# AD9833_Diff_Output_Current_Source.net
KiCad netlist of a schematic drawn in Altium Designer
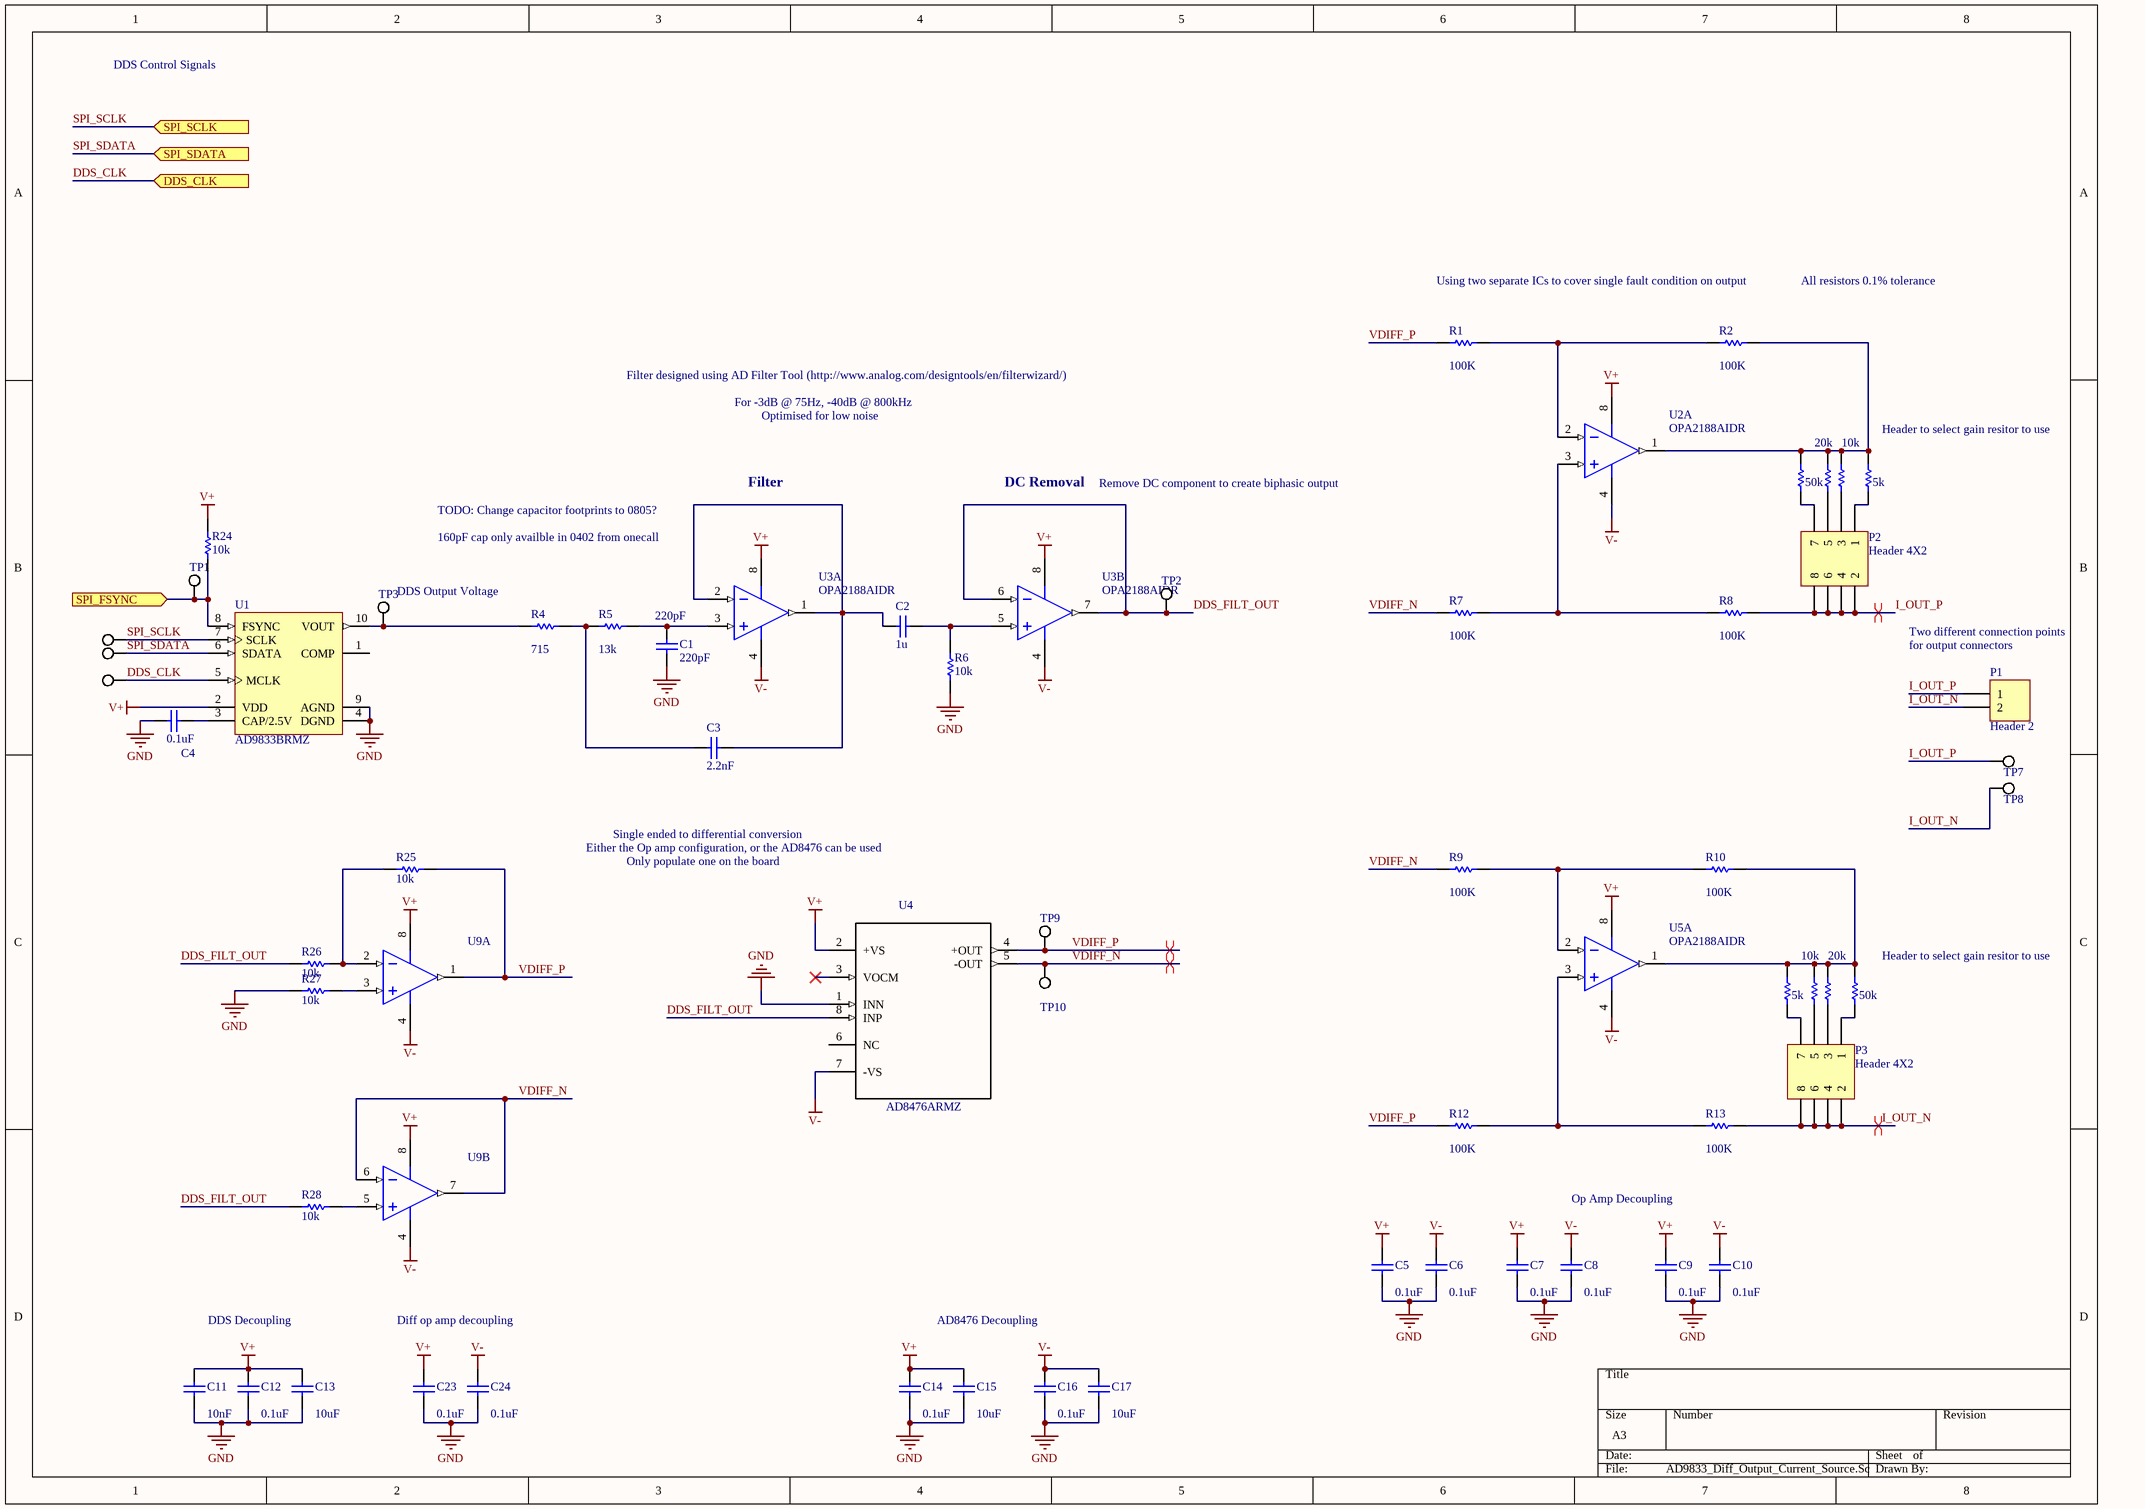
[diagram p0: AD9833_Diff_Output_Current_Source.SchDoc]

(export (version "E")
  (design (tool "Eeschema 10.0.6"))
  (components
    (comp (ref "C1")
      (value "220pF")
      (footprint "1608[0603]")
      (description "Capacitor (Semiconductor SIM Model)")
      (fields (field (name "ALTIUM_VALUE") "220pF") (field (name "PUBLISHER") "Altium Limited"))
      (libsource (lib "Miscellaneous Devices") (part "Cap Semi"))
    )
    (comp (ref "C2")
      (value "1u")
      (footprint "1608[0603]")
      (description "Capacitor (Semiconductor SIM Model)")
      (fields (field (name "PUBLISHER") "Altium Limited"))
      (libsource (lib "Miscellaneous Devices") (part "Cap Semi"))
    )
    (comp (ref "C3")
      (value "2.2nF")
      (footprint "1608[0603]")
      (description "Capacitor (Semiconductor SIM Model)")
      (fields (field (name "PUBLISHER") "Altium Limited"))
      (libsource (lib "Miscellaneous Devices") (part "Cap Semi"))
    )
    (comp (ref "C4")
      (value "0.1uF")
      (footprint "1608[0603]")
      (description "Capacitor (Semiconductor SIM Model)")
      (fields (field (name "PUBLISHER") "Altium Limited"))
      (libsource (lib "Miscellaneous Devices") (part "Cap Semi"))
    )
    (comp (ref "C5")
      (value "0.1uF")
      (footprint "1608[0603]")
      (description "Capacitor (Semiconductor SIM Model)")
      (fields (field (name "PUBLISHER") "Altium Limited"))
      (libsource (lib "Miscellaneous Devices") (part "Cap Semi"))
    )
    (comp (ref "C6")
      (value "0.1uF")
      (footprint "1608[0603]")
      (description "Capacitor (Semiconductor SIM Model)")
      (fields (field (name "PUBLISHER") "Altium Limited"))
      (libsource (lib "Miscellaneous Devices") (part "Cap Semi"))
    )
    (comp (ref "C7")
      (value "0.1uF")
      (footprint "1608[0603]")
      (description "Capacitor (Semiconductor SIM Model)")
      (fields (field (name "PUBLISHER") "Altium Limited"))
      (libsource (lib "Miscellaneous Devices") (part "Cap Semi"))
    )
    (comp (ref "C8")
      (value "0.1uF")
      (footprint "1608[0603]")
      (description "Capacitor (Semiconductor SIM Model)")
      (fields (field (name "PUBLISHER") "Altium Limited"))
      (libsource (lib "Miscellaneous Devices") (part "Cap Semi"))
    )
    (comp (ref "C9")
      (value "0.1uF")
      (footprint "1608[0603]")
      (description "Capacitor (Semiconductor SIM Model)")
      (fields (field (name "PUBLISHER") "Altium Limited"))
      (libsource (lib "Miscellaneous Devices") (part "Cap Semi"))
    )
    (comp (ref "C10")
      (value "0.1uF")
      (footprint "1608[0603]")
      (description "Capacitor (Semiconductor SIM Model)")
      (fields (field (name "PUBLISHER") "Altium Limited"))
      (libsource (lib "Miscellaneous Devices") (part "Cap Semi"))
    )
    (comp (ref "C11")
      (value "10nF")
      (footprint "1608[0603]")
      (description "Capacitor (Semiconductor SIM Model)")
      (fields (field (name "PUBLISHER") "Altium Limited"))
      (libsource (lib "Miscellaneous Devices") (part "Cap Semi"))
    )
    (comp (ref "C12")
      (value "0.1uF")
      (footprint "1608[0603]")
      (description "Capacitor (Semiconductor SIM Model)")
      (fields (field (name "PUBLISHER") "Altium Limited"))
      (libsource (lib "Miscellaneous Devices") (part "Cap Semi"))
    )
    (comp (ref "C13")
      (value "10uF")
      (footprint "1608[0603]")
      (description "Capacitor (Semiconductor SIM Model)")
      (fields (field (name "PUBLISHER") "Altium Limited"))
      (libsource (lib "Miscellaneous Devices") (part "Cap Semi"))
    )
    (comp (ref "C14")
      (value "0.1uF")
      (footprint "1608[0603]")
      (description "Capacitor (Semiconductor SIM Model)")
      (fields (field (name "PUBLISHER") "Altium Limited"))
      (libsource (lib "Miscellaneous Devices") (part "Cap Semi"))
    )
    (comp (ref "C15")
      (value "10uF")
      (footprint "1608[0603]")
      (description "Capacitor (Semiconductor SIM Model)")
      (fields (field (name "PUBLISHER") "Altium Limited"))
      (libsource (lib "Miscellaneous Devices") (part "Cap Semi"))
    )
    (comp (ref "C16")
      (value "0.1uF")
      (footprint "1608[0603]")
      (description "Capacitor (Semiconductor SIM Model)")
      (fields (field (name "PUBLISHER") "Altium Limited"))
      (libsource (lib "Miscellaneous Devices") (part "Cap Semi"))
    )
    (comp (ref "C17")
      (value "10uF")
      (footprint "1608[0603]")
      (description "Capacitor (Semiconductor SIM Model)")
      (fields (field (name "PUBLISHER") "Altium Limited"))
      (libsource (lib "Miscellaneous Devices") (part "Cap Semi"))
    )
    (comp (ref "C23")
      (value "0.1uF")
      (footprint "1608[0603]")
      (description "Capacitor (Semiconductor SIM Model)")
      (fields (field (name "PUBLISHER") "Altium Limited"))
      (libsource (lib "Miscellaneous Devices") (part "Cap Semi"))
    )
    (comp (ref "C24")
      (value "0.1uF")
      (footprint "1608[0603]")
      (description "Capacitor (Semiconductor SIM Model)")
      (fields (field (name "PUBLISHER") "Altium Limited"))
      (libsource (lib "Miscellaneous Devices") (part "Cap Semi"))
    )
    (comp (ref "P1")
      (value "Header 2")
      (footprint "HDR1X2")
      (description "Header, 2-Pin")
      (fields (field (name "PUBLISHER") "Altium Limited"))
      (libsource (lib "Miscellaneous Connectors") (part "Header 2"))
    )
    (comp (ref "P2")
      (value "Header 4X2")
      (footprint "HDR2X4")
      (description "Header, 4-Pin, Dual row")
      (fields (field (name "PUBLISHER") "Altium Limited"))
      (libsource (lib "Miscellaneous Connectors") (part "Header 4X2"))
    )
    (comp (ref "P3")
      (value "Header 4X2")
      (footprint "HDR2X4")
      (description "Header, 4-Pin, Dual row")
      (fields (field (name "PUBLISHER") "Altium Limited"))
      (libsource (lib "Miscellaneous Connectors") (part "Header 4X2"))
    )
    (comp (ref "R1")
      (value "100K")
      (footprint "6-0805_M")
      (description "Resistor")
      (fields (field (name "PUBLISHER") "Altium Limited"))
      (libsource (lib "Miscellaneous Devices") (part "Res1"))
    )
    (comp (ref "R2")
      (value "100K")
      (footprint "6-0805_M")
      (description "Resistor")
      (fields (field (name "PUBLISHER") "Altium Limited"))
      (libsource (lib "Miscellaneous Devices") (part "Res1"))
    )
    (comp (ref "R3")
      (value "50k")
      (footprint "6-0805_M")
      (description "Resistor")
      (fields (field (name "PUBLISHER") "Altium Limited"))
      (libsource (lib "Miscellaneous Devices") (part "Res1"))
    )
    (comp (ref "R4")
      (value "715")
      (footprint "6-0805_M")
      (description "Resistor")
      (fields (field (name "PUBLISHER") "Altium Limited"))
      (libsource (lib "Miscellaneous Devices") (part "Res1"))
    )
    (comp (ref "R5")
      (value "13k")
      (footprint "6-0805_M")
      (description "Resistor")
      (fields (field (name "PUBLISHER") "Altium Limited"))
      (libsource (lib "Miscellaneous Devices") (part "Res1"))
    )
    (comp (ref "R6")
      (value "10k")
      (footprint "6-0805_M")
      (description "Resistor")
      (fields (field (name "PUBLISHER") "Altium Limited"))
      (libsource (lib "Miscellaneous Devices") (part "Res1"))
    )
    (comp (ref "R7")
      (value "100K")
      (footprint "6-0805_M")
      (description "Resistor")
      (fields (field (name "PUBLISHER") "Altium Limited"))
      (libsource (lib "Miscellaneous Devices") (part "Res1"))
    )
    (comp (ref "R8")
      (value "100K")
      (footprint "6-0805_M")
      (description "Resistor")
      (fields (field (name "PUBLISHER") "Altium Limited"))
      (libsource (lib "Miscellaneous Devices") (part "Res1"))
    )
    (comp (ref "R9")
      (value "100K")
      (footprint "6-0805_M")
      (description "Resistor")
      (fields (field (name "PUBLISHER") "Altium Limited"))
      (libsource (lib "Miscellaneous Devices") (part "Res1"))
    )
    (comp (ref "R10")
      (value "100K")
      (footprint "6-0805_M")
      (description "Resistor")
      (fields (field (name "PUBLISHER") "Altium Limited"))
      (libsource (lib "Miscellaneous Devices") (part "Res1"))
    )
    (comp (ref "R11")
      (value "20k")
      (footprint "6-0805_M")
      (description "Resistor")
      (fields (field (name "PUBLISHER") "Altium Limited"))
      (libsource (lib "Miscellaneous Devices") (part "Res1"))
    )
    (comp (ref "R12")
      (value "100K")
      (footprint "6-0805_M")
      (description "Resistor")
      (fields (field (name "PUBLISHER") "Altium Limited"))
      (libsource (lib "Miscellaneous Devices") (part "Res1"))
    )
    (comp (ref "R13")
      (value "100K")
      (footprint "6-0805_M")
      (description "Resistor")
      (fields (field (name "PUBLISHER") "Altium Limited"))
      (libsource (lib "Miscellaneous Devices") (part "Res1"))
    )
    (comp (ref "R18")
      (value "10k")
      (footprint "6-0805_M")
      (description "Resistor")
      (fields (field (name "PUBLISHER") "Altium Limited"))
      (libsource (lib "Miscellaneous Devices") (part "Res1"))
    )
    (comp (ref "R19")
      (value "5k")
      (footprint "6-0805_M")
      (description "Resistor")
      (fields (field (name "PUBLISHER") "Altium Limited"))
      (libsource (lib "Miscellaneous Devices") (part "Res1"))
    )
    (comp (ref "R20")
      (value "5k")
      (footprint "6-0805_M")
      (description "Resistor")
      (fields (field (name "PUBLISHER") "Altium Limited"))
      (libsource (lib "Miscellaneous Devices") (part "Res1"))
    )
    (comp (ref "R21")
      (value "10k")
      (footprint "6-0805_M")
      (description "Resistor")
      (fields (field (name "PUBLISHER") "Altium Limited"))
      (libsource (lib "Miscellaneous Devices") (part "Res1"))
    )
    (comp (ref "R22")
      (value "20k")
      (footprint "6-0805_M")
      (description "Resistor")
      (fields (field (name "PUBLISHER") "Altium Limited"))
      (libsource (lib "Miscellaneous Devices") (part "Res1"))
    )
    (comp (ref "R23")
      (value "50k")
      (footprint "6-0805_M")
      (description "Resistor")
      (fields (field (name "PUBLISHER") "Altium Limited"))
      (libsource (lib "Miscellaneous Devices") (part "Res1"))
    )
    (comp (ref "R24")
      (value "10k")
      (footprint "6-0805_M")
      (description "Resistor")
      (fields (field (name "PUBLISHER") "Altium Limited"))
      (libsource (lib "Miscellaneous Devices") (part "Res1"))
    )
    (comp (ref "R25")
      (value "10k")
      (footprint "6-0805_M")
      (description "Resistor")
      (fields (field (name "PUBLISHER") "Altium Limited"))
      (libsource (lib "Miscellaneous Devices") (part "Res1"))
    )
    (comp (ref "R26")
      (value "10k")
      (footprint "6-0805_M")
      (description "Resistor")
      (fields (field (name "PUBLISHER") "Altium Limited"))
      (libsource (lib "Miscellaneous Devices") (part "Res1"))
    )
    (comp (ref "R27")
      (value "10k")
      (footprint "6-0805_M")
      (description "Resistor")
      (fields (field (name "PUBLISHER") "Altium Limited"))
      (libsource (lib "Miscellaneous Devices") (part "Res1"))
    )
    (comp (ref "R28")
      (value "10k")
      (footprint "6-0805_M")
      (description "Resistor")
      (fields (field (name "PUBLISHER") "Altium Limited"))
      (libsource (lib "Miscellaneous Devices") (part "Res1"))
    )
    (comp (ref "TP1")
      (value "TESTPOINT_WHITE")
      (footprint "TestPointVia")
      (libsource (lib "altium-import") (part "root_0_TESTPOINT_WHITE_"))
    )
    (comp (ref "TP2")
      (value "TESTPOINT_WHITE")
      (footprint "TestPointVia")
      (libsource (lib "altium-import") (part "root_0_TESTPOINT_WHITE_"))
    )
    (comp (ref "TP3")
      (value "TESTPOINT_WHITE")
      (footprint "TestPointVia")
      (libsource (lib "altium-import") (part "root_0_TESTPOINT_WHITE_"))
    )
    (comp (ref "TP4")
      (value "TESTPOINT_WHITE")
      (footprint "TestPointVia")
      (libsource (lib "altium-import") (part "root_1_TESTPOINT_WHITE_"))
    )
    (comp (ref "TP5")
      (value "TESTPOINT_WHITE")
      (footprint "TestPointVia")
      (libsource (lib "altium-import") (part "root_1_TESTPOINT_WHITE_"))
    )
    (comp (ref "TP6")
      (value "TESTPOINT_WHITE")
      (footprint "TestPointVia")
      (libsource (lib "altium-import") (part "root_1_TESTPOINT_WHITE_"))
    )
    (comp (ref "TP7")
      (value "TESTPOINT_WHITE")
      (footprint "TestPointVia")
      (libsource (lib "altium-import") (part "root_3_TESTPOINT_WHITE_"))
    )
    (comp (ref "TP8")
      (value "TESTPOINT_WHITE")
      (footprint "TestPointVia")
      (libsource (lib "altium-import") (part "root_3_TESTPOINT_WHITE_"))
    )
    (comp (ref "TP9")
      (value "TESTPOINT_WHITE")
      (footprint "TestPointVia")
      (libsource (lib "altium-import") (part "root_0_TESTPOINT_WHITE_"))
    )
    (comp (ref "TP10")
      (value "TESTPOINT_WHITE")
      (footprint "TestPointVia")
      (libsource (lib "altium-import") (part "root_2_TESTPOINT_WHITE_"))
    )
    (comp (ref "U1")
      (value "AD9833BRMZ")
      (footprint "ADI-RM-10_M")
      (libsource (lib "Altium Content Vault") (part "ADI-AD9833-RM-10"))
    )
    (comp (ref "U2")
      (value "OPA2188AIDR")
      (footprint "D0008A_L")
      (fields (field (name "MANUFACTURER") "Texas Instruments"))
      (libsource (lib "Altium Content Vault") (part "CMP-0272-00241-3"))
    )
    (comp (ref "U3")
      (value "OPA2188AIDR")
      (footprint "D0008A_L")
      (fields (field (name "MANUFACTURER") "Texas Instruments"))
      (libsource (lib "Altium Content Vault") (part "TI-OPA-8_2"))
    )
    (comp (ref "U4")
      (value "AD8476ARMZ")
      (footprint "SOP65P490X110-8N")
      (description "SP Amp DIFF AMP Single R-R O/P Â±9V/18V 8-Pin MSOP Tube")
      (fields (field (name "MF") "Analog Devices"))
      (libsource (lib "AD8476ARMZ") (part "AD8476ARMZ"))
    )
    (comp (ref "U5")
      (value "OPA2188AIDR")
      (footprint "D0008A_L")
      (fields (field (name "MANUFACTURER") "Texas Instruments"))
      (libsource (lib "Altium Content Vault") (part "TI-OPA-8_2"))
    )
    (comp (ref "U9")
      (value "OPA2188AIDR")
      (footprint "D0008A_L")
      (fields (field (name "MANUFACTURER") "Texas Instruments"))
      (libsource (lib "Altium Content Vault") (part "CMP-0272-00241-3"))
    )
  )
  (nets
    (net (code "1") (name "/DDS_CLK") (class "Default")
      (node (ref "TP6") (pin "1") (pinfunction "1_1") (pintype "passive"))
      (node (ref "U1") (pin "5") (pinfunction "MCLK_5") (pintype "input"))
    )
    (net (code "2") (name "/DDS_FILT_OUT") (class "Default")
      (node (ref "R26") (pin "2") (pinfunction "2_2") (pintype "passive"))
      (node (ref "R28") (pin "2") (pinfunction "2_2") (pintype "passive"))
      (node (ref "TP2") (pin "1") (pinfunction "1_1") (pintype "passive"))
      (node (ref "U3") (pin "6") (pinfunction "IN_B-_6") (pintype "input"))
      (node (ref "U3") (pin "7") (pinfunction "OUT_B_7") (pintype "output"))
      (node (ref "U4") (pin "8") (pinfunction "INP_8") (pintype "input"))
    )
    (net (code "3") (name "/I_OUT_N") (class "Default")
      (node (ref "P1") (pin "2") (pinfunction "2_2") (pintype "passive"))
      (node (ref "P3") (pin "2") (pinfunction "2_2") (pintype "passive"))
      (node (ref "P3") (pin "4") (pinfunction "4_4") (pintype "passive"))
      (node (ref "P3") (pin "6") (pinfunction "6_6") (pintype "passive"))
      (node (ref "P3") (pin "8") (pinfunction "8_8") (pintype "passive"))
      (node (ref "R13") (pin "2") (pinfunction "2_2") (pintype "passive"))
      (node (ref "TP8") (pin "1") (pinfunction "1_1") (pintype "passive"))
    )
    (net (code "4") (name "/I_OUT_P") (class "Default")
      (node (ref "P1") (pin "1") (pinfunction "1_1") (pintype "passive"))
      (node (ref "P2") (pin "2") (pinfunction "2_2") (pintype "passive"))
      (node (ref "P2") (pin "4") (pinfunction "4_4") (pintype "passive"))
      (node (ref "P2") (pin "6") (pinfunction "6_6") (pintype "passive"))
      (node (ref "P2") (pin "8") (pinfunction "8_8") (pintype "passive"))
      (node (ref "R8") (pin "2") (pinfunction "2_2") (pintype "passive"))
      (node (ref "TP7") (pin "1") (pinfunction "1_1") (pintype "passive"))
    )
    (net (code "5") (name "/SPI_FSYNC") (class "Default")
      (node (ref "R24") (pin "1") (pinfunction "1_1") (pintype "passive"))
      (node (ref "TP1") (pin "1") (pinfunction "1_1") (pintype "passive"))
      (node (ref "U1") (pin "8") (pinfunction "FSYNC_8") (pintype "input"))
    )
    (net (code "6") (name "/SPI_SCLK") (class "Default")
      (node (ref "TP4") (pin "1") (pinfunction "1_1") (pintype "passive"))
      (node (ref "U1") (pin "7") (pinfunction "SCLK_7") (pintype "input"))
    )
    (net (code "7") (name "/SPI_SDATA") (class "Default")
      (node (ref "TP5") (pin "1") (pinfunction "1_1") (pintype "passive"))
      (node (ref "U1") (pin "6") (pinfunction "SDATA_6") (pintype "input"))
    )
    (net (code "8") (name "/VDIFF_N") (class "Default")
      (node (ref "R7") (pin "1") (pinfunction "1_1") (pintype "passive"))
      (node (ref "R9") (pin "1") (pinfunction "1_1") (pintype "passive"))
      (node (ref "TP10") (pin "1") (pinfunction "1_1") (pintype "passive"))
      (node (ref "U4") (pin "5") (pinfunction "-OUT_5") (pintype "output"))
      (node (ref "U9") (pin "6") (pinfunction "IN_B-_6") (pintype "input"))
      (node (ref "U9") (pin "7") (pinfunction "OUT_B_7") (pintype "output"))
    )
    (net (code "9") (name "/VDIFF_P") (class "Default")
      (node (ref "R1") (pin "1") (pinfunction "1_1") (pintype "passive"))
      (node (ref "R12") (pin "1") (pinfunction "1_1") (pintype "passive"))
      (node (ref "R25") (pin "1") (pinfunction "1_1") (pintype "passive"))
      (node (ref "TP9") (pin "1") (pinfunction "1_1") (pintype "passive"))
      (node (ref "U4") (pin "4") (pinfunction "+OUT_4") (pintype "output"))
      (node (ref "U9") (pin "1") (pinfunction "OUT_A_1") (pintype "output"))
    )
    (net (code "10") (name "GND") (class "Default")
      (node (ref "C1") (pin "1") (pinfunction "1_1") (pintype "passive"))
      (node (ref "C10") (pin "1") (pinfunction "1_1") (pintype "passive"))
      (node (ref "C11") (pin "1") (pinfunction "1_1") (pintype "passive"))
      (node (ref "C12") (pin "1") (pinfunction "1_1") (pintype "passive"))
      (node (ref "C13") (pin "1") (pinfunction "1_1") (pintype "passive"))
      (node (ref "C14") (pin "1") (pinfunction "1_1") (pintype "passive"))
      (node (ref "C15") (pin "1") (pinfunction "1_1") (pintype "passive"))
      (node (ref "C16") (pin "1") (pinfunction "1_1") (pintype "passive"))
      (node (ref "C17") (pin "1") (pinfunction "1_1") (pintype "passive"))
      (node (ref "C23") (pin "1") (pinfunction "1_1") (pintype "passive"))
      (node (ref "C24") (pin "1") (pinfunction "1_1") (pintype "passive"))
      (node (ref "C4") (pin "1") (pinfunction "1_1") (pintype "passive"))
      (node (ref "C5") (pin "1") (pinfunction "1_1") (pintype "passive"))
      (node (ref "C6") (pin "1") (pinfunction "1_1") (pintype "passive"))
      (node (ref "C7") (pin "1") (pinfunction "1_1") (pintype "passive"))
      (node (ref "C8") (pin "1") (pinfunction "1_1") (pintype "passive"))
      (node (ref "C9") (pin "1") (pinfunction "1_1") (pintype "passive"))
      (node (ref "R27") (pin "2") (pinfunction "2_2") (pintype "passive"))
      (node (ref "R6") (pin "1") (pinfunction "1_1") (pintype "passive"))
      (node (ref "U1") (pin "4") (pinfunction "DGND_4") (pintype "power_in"))
      (node (ref "U1") (pin "9") (pinfunction "AGND_9") (pintype "power_in"))
      (node (ref "U4") (pin "1") (pinfunction "INN_1") (pintype "input"))
    )
    (net (code "11") (name "Net-(C3-Pad2)") (class "Default")
      (node (ref "C3") (pin "2") (pinfunction "2_2") (pintype "passive"))
      (node (ref "R4") (pin "2") (pinfunction "2_2") (pintype "passive"))
      (node (ref "R5") (pin "1") (pinfunction "1_1") (pintype "passive"))
    )
    (net (code "12") (name "Net-(P2-Pad1)") (class "Default")
      (node (ref "P2") (pin "1") (pinfunction "1_1") (pintype "passive"))
      (node (ref "R19") (pin "2") (pinfunction "2_2") (pintype "passive"))
    )
    (net (code "13") (name "Net-(P2-Pad3)") (class "Default")
      (node (ref "P2") (pin "3") (pinfunction "3_3") (pintype "passive"))
      (node (ref "R18") (pin "2") (pinfunction "2_2") (pintype "passive"))
    )
    (net (code "14") (name "Net-(P2-Pad5)") (class "Default")
      (node (ref "P2") (pin "5") (pinfunction "5_5") (pintype "passive"))
      (node (ref "R11") (pin "2") (pinfunction "2_2") (pintype "passive"))
    )
    (net (code "15") (name "Net-(P2-Pad7)") (class "Default")
      (node (ref "P2") (pin "7") (pinfunction "7_7") (pintype "passive"))
      (node (ref "R3") (pin "1") (pinfunction "1_1") (pintype "passive"))
    )
    (net (code "16") (name "Net-(P3-Pad1)") (class "Default")
      (node (ref "P3") (pin "1") (pinfunction "1_1") (pintype "passive"))
      (node (ref "R23") (pin "1") (pinfunction "1_1") (pintype "passive"))
    )
    (net (code "17") (name "Net-(P3-Pad3)") (class "Default")
      (node (ref "P3") (pin "3") (pinfunction "3_3") (pintype "passive"))
      (node (ref "R22") (pin "2") (pinfunction "2_2") (pintype "passive"))
    )
    (net (code "18") (name "Net-(P3-Pad5)") (class "Default")
      (node (ref "P3") (pin "5") (pinfunction "5_5") (pintype "passive"))
      (node (ref "R21") (pin "2") (pinfunction "2_2") (pintype "passive"))
    )
    (net (code "19") (name "Net-(P3-Pad7)") (class "Default")
      (node (ref "P3") (pin "7") (pinfunction "7_7") (pintype "passive"))
      (node (ref "R20") (pin "2") (pinfunction "2_2") (pintype "passive"))
    )
    (net (code "20") (name "Net-(U1-CAP{slash}2.5V)") (class "Default")
      (node (ref "C4") (pin "2") (pinfunction "2_2") (pintype "passive"))
      (node (ref "U1") (pin "3") (pinfunction "CAP/2.5V_3") (pintype "power_in"))
    )
    (net (code "21") (name "Net-(U1-VOUT)") (class "Default")
      (node (ref "R4") (pin "1") (pinfunction "1_1") (pintype "passive"))
      (node (ref "TP3") (pin "1") (pinfunction "1_1") (pintype "passive"))
      (node (ref "U1") (pin "10") (pinfunction "VOUT_10") (pintype "output"))
    )
    (net (code "22") (name "Net-(U2A-IN_A+)") (class "Default")
      (node (ref "R7") (pin "2") (pinfunction "2_2") (pintype "passive"))
      (node (ref "R8") (pin "1") (pinfunction "1_1") (pintype "passive"))
      (node (ref "U2") (pin "3") (pinfunction "IN_A+_3") (pintype "input"))
    )
    (net (code "23") (name "Net-(U2A-IN_A-)") (class "Default")
      (node (ref "R1") (pin "2") (pinfunction "2_2") (pintype "passive"))
      (node (ref "R2") (pin "1") (pinfunction "1_1") (pintype "passive"))
      (node (ref "U2") (pin "2") (pinfunction "IN_A-_2") (pintype "input"))
    )
    (net (code "24") (name "Net-(U2A-OUT_A)") (class "Default")
      (node (ref "R11") (pin "1") (pinfunction "1_1") (pintype "passive"))
      (node (ref "R18") (pin "1") (pinfunction "1_1") (pintype "passive"))
      (node (ref "R19") (pin "1") (pinfunction "1_1") (pintype "passive"))
      (node (ref "R2") (pin "2") (pinfunction "2_2") (pintype "passive"))
      (node (ref "R3") (pin "2") (pinfunction "2_2") (pintype "passive"))
      (node (ref "U2") (pin "1") (pinfunction "OUT_A_1") (pintype "output"))
    )
    (net (code "25") (name "Net-(U3A-IN_A+)") (class "Default")
      (node (ref "C1") (pin "2") (pinfunction "2_2") (pintype "passive"))
      (node (ref "R5") (pin "2") (pinfunction "2_2") (pintype "passive"))
      (node (ref "U3") (pin "3") (pinfunction "IN_A+_3") (pintype "input"))
    )
    (net (code "26") (name "Net-(U3A-IN_A-)") (class "Default")
      (node (ref "C2") (pin "1") (pinfunction "1_1") (pintype "passive"))
      (node (ref "C3") (pin "1") (pinfunction "1_1") (pintype "passive"))
      (node (ref "U3") (pin "1") (pinfunction "OUT_A_1") (pintype "output"))
      (node (ref "U3") (pin "2") (pinfunction "IN_A-_2") (pintype "input"))
    )
    (net (code "27") (name "Net-(U3B-IN_B+)") (class "Default")
      (node (ref "C2") (pin "2") (pinfunction "2_2") (pintype "passive"))
      (node (ref "R6") (pin "2") (pinfunction "2_2") (pintype "passive"))
      (node (ref "U3") (pin "5") (pinfunction "IN_B+_5") (pintype "input"))
    )
    (net (code "28") (name "Net-(U5A-IN_A+)") (class "Default")
      (node (ref "R12") (pin "2") (pinfunction "2_2") (pintype "passive"))
      (node (ref "R13") (pin "1") (pinfunction "1_1") (pintype "passive"))
      (node (ref "U5") (pin "3") (pinfunction "IN_A+_3") (pintype "input"))
    )
    (net (code "29") (name "Net-(U5A-IN_A-)") (class "Default")
      (node (ref "R10") (pin "1") (pinfunction "1_1") (pintype "passive"))
      (node (ref "R9") (pin "2") (pinfunction "2_2") (pintype "passive"))
      (node (ref "U5") (pin "2") (pinfunction "IN_A-_2") (pintype "input"))
    )
    (net (code "30") (name "Net-(U5A-OUT_A)") (class "Default")
      (node (ref "R10") (pin "2") (pinfunction "2_2") (pintype "passive"))
      (node (ref "R20") (pin "1") (pinfunction "1_1") (pintype "passive"))
      (node (ref "R21") (pin "1") (pinfunction "1_1") (pintype "passive"))
      (node (ref "R22") (pin "1") (pinfunction "1_1") (pintype "passive"))
      (node (ref "R23") (pin "2") (pinfunction "2_2") (pintype "passive"))
      (node (ref "U5") (pin "1") (pinfunction "OUT_A_1") (pintype "output"))
    )
    (net (code "31") (name "Net-(U9A-IN_A+)") (class "Default")
      (node (ref "R27") (pin "1") (pinfunction "1_1") (pintype "passive"))
      (node (ref "U9") (pin "3") (pinfunction "IN_A+_3") (pintype "input"))
    )
    (net (code "32") (name "Net-(U9A-IN_A-)") (class "Default")
      (node (ref "R25") (pin "2") (pinfunction "2_2") (pintype "passive"))
      (node (ref "R26") (pin "1") (pinfunction "1_1") (pintype "passive"))
      (node (ref "U9") (pin "2") (pinfunction "IN_A-_2") (pintype "input"))
    )
    (net (code "33") (name "Net-(U9B-IN_B+)") (class "Default")
      (node (ref "R28") (pin "1") (pinfunction "1_1") (pintype "passive"))
      (node (ref "U9") (pin "5") (pinfunction "IN_B+_5") (pintype "input"))
    )
    (net (code "34") (name "V+") (class "Default")
      (node (ref "C11") (pin "2") (pinfunction "2_2") (pintype "passive"))
      (node (ref "C12") (pin "2") (pinfunction "2_2") (pintype "passive"))
      (node (ref "C13") (pin "2") (pinfunction "2_2") (pintype "passive"))
      (node (ref "C14") (pin "2") (pinfunction "2_2") (pintype "passive"))
      (node (ref "C15") (pin "2") (pinfunction "2_2") (pintype "passive"))
      (node (ref "C23") (pin "2") (pinfunction "2_2") (pintype "passive"))
      (node (ref "C5") (pin "2") (pinfunction "2_2") (pintype "passive"))
      (node (ref "C7") (pin "2") (pinfunction "2_2") (pintype "passive"))
      (node (ref "C9") (pin "2") (pinfunction "2_2") (pintype "passive"))
      (node (ref "R24") (pin "2") (pinfunction "2_2") (pintype "passive"))
      (node (ref "U1") (pin "2") (pinfunction "VDD_2") (pintype "power_in"))
      (node (ref "U2") (pin "8") (pinfunction "V+_8") (pintype "power_in"))
      (node (ref "U3") (pin "8") (pinfunction "V+_8") (pintype "power_in"))
      (node (ref "U4") (pin "2") (pinfunction "+VS_2") (pintype "power_in"))
      (node (ref "U5") (pin "8") (pinfunction "V+_8") (pintype "power_in"))
      (node (ref "U9") (pin "8") (pinfunction "V+_8") (pintype "power_in"))
    )
    (net (code "35") (name "V-") (class "Default")
      (node (ref "C10") (pin "2") (pinfunction "2_2") (pintype "passive"))
      (node (ref "C16") (pin "2") (pinfunction "2_2") (pintype "passive"))
      (node (ref "C17") (pin "2") (pinfunction "2_2") (pintype "passive"))
      (node (ref "C24") (pin "2") (pinfunction "2_2") (pintype "passive"))
      (node (ref "C6") (pin "2") (pinfunction "2_2") (pintype "passive"))
      (node (ref "C8") (pin "2") (pinfunction "2_2") (pintype "passive"))
      (node (ref "U2") (pin "4") (pinfunction "V-_4") (pintype "power_in"))
      (node (ref "U3") (pin "4") (pinfunction "V-_4") (pintype "power_in"))
      (node (ref "U4") (pin "7") (pinfunction "-VS_7") (pintype "power_in"))
      (node (ref "U5") (pin "4") (pinfunction "V-_4") (pintype "power_in"))
      (node (ref "U9") (pin "4") (pinfunction "V-_4") (pintype "power_in"))
    )
    (net (code "36") (name "unconnected-(U1-COMP-Pad1)") (class "Default")
      (node (ref "U1") (pin "1") (pinfunction "COMP_1") (pintype "passive"))
    )
    (net (code "37") (name "unconnected-(U4-NC-Pad6)") (class "Default")
      (node (ref "U4") (pin "6") (pinfunction "NC_6") (pintype "passive"))
    )
    (net (code "38") (name "unconnected-(U4-VOCM-Pad3)") (class "Default")
      (node (ref "U4") (pin "3") (pinfunction "VOCM_3") (pintype "input+no_connect"))
    )
  )
)
